# SAMD51_DevBoard.net
KiCad netlist of a schematic drawn in Altium Designer
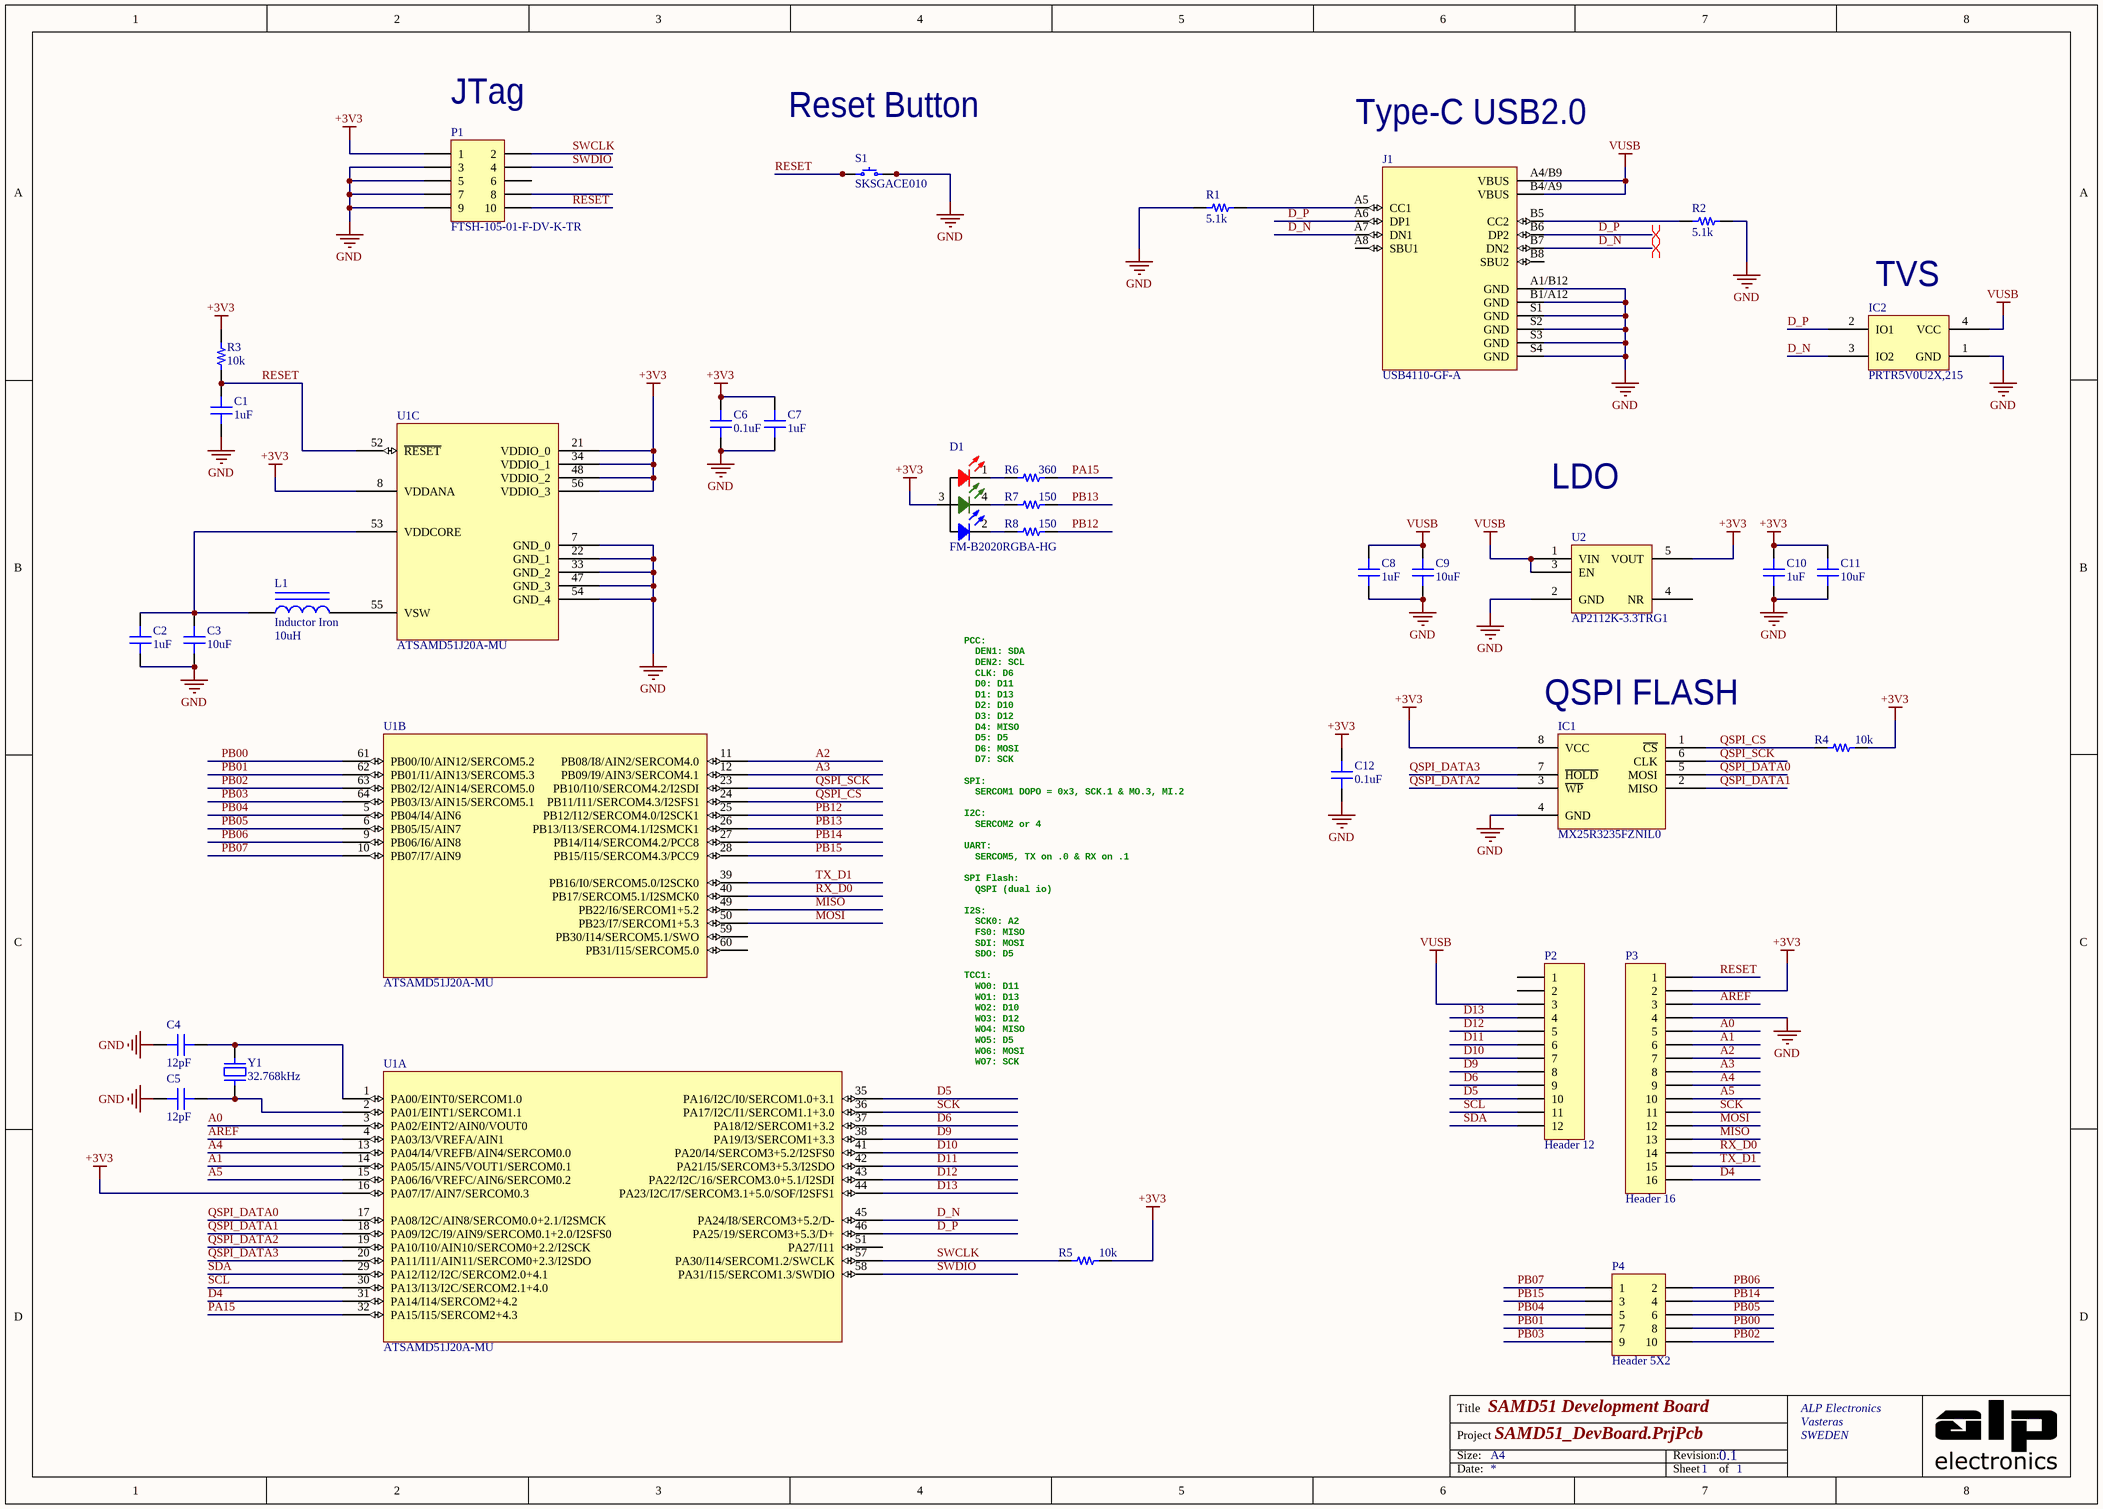
[diagram p0: SAMD51_DevBoard.SchDoc]

(export (version "E")
  (design (tool "Eeschema 10.0.6"))
  (components
    (comp (ref "C1")
      (value "1uF")
      (footprint "CAP 0603/1608")
      (description "CAP CER 1UF 16V X5R 0603")
      (fields (field (name "PART NUMBER") "C0603C105K4PACTU") (field (name "MANUFACTURER") "Kemet"))
      (libsource (lib "Celestial Library Database") (part "Capacitor"))
    )
    (comp (ref "C2")
      (value "1uF")
      (footprint "CAP 0603/1608")
      (description "CAP CER 1UF 16V X5R 0603")
      (fields (field (name "PART NUMBER") "C0603C105K4PACTU") (field (name "MANUFACTURER") "Kemet"))
      (libsource (lib "Celestial Library Database") (part "Capacitor"))
    )
    (comp (ref "C3")
      (value "10uF")
      (footprint "CAP 0603/1608")
      (description "CAP CER 10UF 6.3V X5R 0603")
      (fields
        (field (name "PART NUMBER") "GRM188R60J106ME47D")
        (field (name "MANUFACTURER") "Murata Electronics North America")
      )
      (libsource (lib "Celestial Library Database") (part "Capacitor"))
    )
    (comp (ref "C4")
      (value "12pF")
      (footprint "CAP 0603/1608")
      (description "CAP CER 12PF 50V C0G 0603")
      (fields
        (field (name "PART NUMBER") "C1608C0G1H120J080AA")
        (field (name "MANUFACTURER") "TDK Corporation")
      )
      (libsource (lib "Celestial Library Database") (part "Capacitor"))
    )
    (comp (ref "C5")
      (value "12pF")
      (footprint "CAP 0603/1608")
      (description "CAP CER 12PF 50V C0G 0603")
      (fields
        (field (name "PART NUMBER") "C1608C0G1H120J080AA")
        (field (name "MANUFACTURER") "TDK Corporation")
      )
      (libsource (lib "Celestial Library Database") (part "Capacitor"))
    )
    (comp (ref "C6")
      (value "0.1uF")
      (footprint "CAP 0603/1608")
      (description "CAP CER 0.1UF 16V X7R 0603")
      (fields
        (field (name "PART NUMBER") "CL10B104JO8NNNC")
        (field (name "MANUFACTURER") "Samsung Electro-Mechanics America, Inc.")
      )
      (libsource (lib "Celestial Library Database") (part "Capacitor"))
    )
    (comp (ref "C7")
      (value "1uF")
      (footprint "CAP 0603/1608")
      (description "CAP CER 1UF 16V X5R 0603")
      (fields (field (name "PART NUMBER") "C0603C105K4PACTU") (field (name "MANUFACTURER") "Kemet"))
      (libsource (lib "Celestial Library Database") (part "Capacitor"))
    )
    (comp (ref "C8")
      (value "1uF")
      (footprint "CAP 0603/1608")
      (description "CAP CER 1UF 16V X5R 0603")
      (fields (field (name "PART NUMBER") "C0603C105K4PACTU") (field (name "MANUFACTURER") "Kemet"))
      (libsource (lib "Celestial Library Database") (part "Capacitor"))
    )
    (comp (ref "C9")
      (value "10uF")
      (footprint "CAP 0603/1608")
      (description "CAP CER 10UF 6.3V X5R 0603")
      (fields
        (field (name "PART NUMBER") "GRM188R60J106ME47D")
        (field (name "MANUFACTURER") "Murata Electronics North America")
      )
      (libsource (lib "Celestial Library Database") (part "Capacitor"))
    )
    (comp (ref "C10")
      (value "1uF")
      (footprint "CAP 0603/1608")
      (description "CAP CER 1UF 16V X5R 0603")
      (fields (field (name "PART NUMBER") "C0603C105K4PACTU") (field (name "MANUFACTURER") "Kemet"))
      (libsource (lib "Celestial Library Database") (part "Capacitor"))
    )
    (comp (ref "C11")
      (value "10uF")
      (footprint "CAP 0603/1608")
      (description "CAP CER 10UF 6.3V X5R 0603")
      (fields
        (field (name "PART NUMBER") "GRM188R60J106ME47D")
        (field (name "MANUFACTURER") "Murata Electronics North America")
      )
      (libsource (lib "Celestial Library Database") (part "Capacitor"))
    )
    (comp (ref "C12")
      (value "0.1uF")
      (footprint "CAP 0603/1608")
      (description "CAP CER 0.1UF 16V X7R 0603")
      (fields
        (field (name "PART NUMBER") "CL10B104JO8NNNC")
        (field (name "MANUFACTURER") "Samsung Electro-Mechanics America, Inc.")
      )
      (libsource (lib "Celestial Library Database") (part "Capacitor"))
    )
    (comp (ref "D1")
      (value "FM-B2020RGBA-HG")
      (footprint "FM-B2020RGBA-HG")
      (description "RGB 615~630nmRed,515~535nmGreen,465~480nmBlue 2020")
      (fields (field (name "MANUFACTURER") "Foshan NationStar Optoelectronics"))
      (libsource (lib "Celestial Library Database") (part "RGB LED 4PIN"))
    )
    (comp (ref "IC1")
      (value "MX25R3235FZNIL0")
      (footprint "SPANSION WSON-8 6x5MM")
      (description "IC FLASH MEM 16MB SPI CMOS 8WSON")
      (fields (field (name "PART NUMBER") "S25FL116K0XNFI011") (field (name "MANUFACTURER") "Spansion"))
      (libsource (lib "Celestial Library Database") (part "SPANSION FLASH SPI 8PIN"))
    )
    (comp (ref "IC2")
      (value "PRTR5V0U2X,215")
      (footprint "SOT143B")
      (description "TVS DIODE 5.5VWM SOT143B")
      (fields (field (name "MANUFACTURER") "NXP Semiconductors"))
      (libsource (lib "Celestial Library Database") (part "NXP PRTR5V0U2X"))
    )
    (comp (ref "J1")
      (value "USB4110-GF-A")
      (footprint "USB4110-GF-A")
      (description "CONN USB 2.0 TYPE-C R/A SMT")
      (fields (field (name "MANUFACTURER") "GCT"))
      (libsource (lib "Celestial Library Database") (part "USB4110-GF-A"))
    )
    (comp (ref "L1")
      (value "Inductor Iron")
      (footprint "Component 3D Footprint:IND_Würth_74404020100")
      (description "Magnetic-Core Inductor")
      (fields (field (name "ALTIUM_VALUE") "10uH") (field (name "PUBLISHER") "Altium Limited"))
      (libsource (lib "Miscellaneous Devices") (part "Inductor Iron"))
    )
    (comp (ref "P1")
      (value "FTSH-105-01-F-DV-K-TR")
      (footprint "3D FootPrint_Backup:FTSH-105-01-F-DV-K-TR")
      (description "Header, 5-Pin, Dual row")
      (fields (field (name "PUBLISHER") "Altium Limited"))
      (libsource (lib "Miscellaneous Connectors") (part "Header 5X2"))
    )
    (comp (ref "P2")
      (value "Header 12")
      (footprint "HDR1X12")
      (description "Header, 12-Pin")
      (fields (field (name "PUBLISHER") "Altium Limited"))
      (libsource (lib "Miscellaneous Connectors") (part "Header 12"))
    )
    (comp (ref "P3")
      (value "Header 16")
      (footprint "HDR1X16")
      (description "Header, 16-Pin")
      (fields (field (name "PUBLISHER") "Altium Limited"))
      (libsource (lib "Miscellaneous Connectors") (part "Header 16"))
    )
    (comp (ref "P4")
      (value "Header 5X2")
      (footprint "HDR2X5")
      (description "Header, 5-Pin, Dual row")
      (fields (field (name "PUBLISHER") "Altium Limited"))
      (libsource (lib "Miscellaneous Connectors") (part "Header 5X2"))
    )
    (comp (ref "R1")
      (value "5.1k")
      (footprint "RES 0603/1608")
      (description "RES SMD 5.1K OHM 5% 1/10W 0603")
      (fields
        (field (name "PART NUMBER") "ERJ-3GEYJ512V")
        (field (name "MANUFACTURER") "Panasonic Electronic Components")
      )
      (libsource (lib "Celestial Library Database") (part "Resistor"))
    )
    (comp (ref "R2")
      (value "5.1k")
      (footprint "RES 0603/1608")
      (description "RES SMD 5.1K OHM 5% 1/10W 0603")
      (fields
        (field (name "PART NUMBER") "ERJ-3GEYJ512V")
        (field (name "MANUFACTURER") "Panasonic Electronic Components")
      )
      (libsource (lib "Celestial Library Database") (part "Resistor"))
    )
    (comp (ref "R3")
      (value "10k")
      (footprint "RES 0603/1608")
      (description "RES SMD 10K OHM 5% 1/10W 0603")
      (fields
        (field (name "PART NUMBER") "ERJ-3GEYJ103V")
        (field (name "MANUFACTURER") "Panasonic Electronic Components")
      )
      (libsource (lib "Celestial Library Database") (part "Resistor"))
    )
    (comp (ref "R4")
      (value "10k")
      (footprint "RES 0603/1608")
      (description "RES SMD 10K OHM 5% 1/10W 0603")
      (fields
        (field (name "PART NUMBER") "ERJ-3GEYJ103V")
        (field (name "MANUFACTURER") "Panasonic Electronic Components")
      )
      (libsource (lib "Celestial Library Database") (part "Resistor"))
    )
    (comp (ref "R5")
      (value "10k")
      (footprint "RES 0603/1608")
      (description "RES SMD 10K OHM 5% 1/10W 0603")
      (fields
        (field (name "PART NUMBER") "ERJ-3GEYJ103V")
        (field (name "MANUFACTURER") "Panasonic Electronic Components")
      )
      (libsource (lib "Celestial Library Database") (part "Resistor"))
    )
    (comp (ref "R6")
      (value "360")
      (footprint "RES 0603/1608")
      (description "RES SMD 360 OHM 5% 1/10W 0603")
      (fields
        (field (name "PART NUMBER") "ERJ-3GEYJ361V")
        (field (name "MANUFACTURER") "Panasonic Electronic Components")
      )
      (libsource (lib "Celestial Library Database") (part "Resistor"))
    )
    (comp (ref "R7")
      (value "150")
      (footprint "RES 0603/1608")
      (description "RES SMD 150 OHM 5% 1/10W 0603")
      (fields
        (field (name "PART NUMBER") "ERJ-3GEYJ151V")
        (field (name "MANUFACTURER") "Panasonic Electronic Components")
      )
      (libsource (lib "Celestial Library Database") (part "Resistor"))
    )
    (comp (ref "R8")
      (value "150")
      (footprint "RES 0603/1608")
      (description "RES SMD 150 OHM 5% 1/10W 0603")
      (fields
        (field (name "PART NUMBER") "ERJ-3GEYJ151V")
        (field (name "MANUFACTURER") "Panasonic Electronic Components")
      )
      (libsource (lib "Celestial Library Database") (part "Resistor"))
    )
    (comp (ref "S1")
      (value "SKSGACE010")
      (footprint "SKSGACE010")
      (description "SWITCH TACTILE SPST-NO 0.05A 16V")
      (fields (field (name "MANUFACTURER") "ALPS"))
      (libsource (lib "Celestial Library Database") (part "SPST-NO 4 PIN"))
    )
    (comp (ref "U1")
      (value "ATSAMD51J20A-MU")
      (footprint "SI LABS QFN-64_S")
      (description "IC MCU 32BIT 1MB FLASH 64VQFN")
      (fields (field (name "MANUFACTURER") "Microchip Technology"))
      (libsource (lib "Celestial Library Database") (part "MicroChip SAM D5x VQFN64"))
    )
    (comp (ref "U2")
      (value "AP2112K-3.3TRG1")
      (footprint "TI SOT-23-5 DBV")
      (description "IC REG LINEAR 3.3V 400MA SOT23-5")
      (fields (field (name "PART NUMBER") "TPS73633DBVT") (field (name "MANUFACTURER") "Texas Instruments"))
      (libsource (lib "Celestial Library Database") (part "TI TPS736xx"))
    )
    (comp (ref "Y1")
      (value "32.768kHz")
      (footprint "ABRACON ABS07")
      (description "CRYSTAL 32.7680KHZ 12.5PF SMD")
      (fields (field (name "PART NUMBER") "ABS07-32.768KHZ-T") (field (name "MANUFACTURER") "Abracon LLC"))
      (libsource (lib "Celestial Library Database") (part "Abracon Crystal ABS07"))
    )
  )
  (nets
    (net (code "1") (name "+3V3") (class "Default")
      (node (ref "C10") (pin "2") (pinfunction "2_2") (pintype "passive"))
      (node (ref "C11") (pin "2") (pinfunction "2_2") (pintype "passive"))
      (node (ref "C12") (pin "2") (pinfunction "2_2") (pintype "passive"))
      (node (ref "C6") (pin "2") (pinfunction "2_2") (pintype "passive"))
      (node (ref "C7") (pin "2") (pinfunction "2_2") (pintype "passive"))
      (node (ref "D1") (pin "3") (pinfunction "3_3") (pintype "passive"))
      (node (ref "IC1") (pin "8") (pinfunction "VCC_8") (pintype "passive"))
      (node (ref "P1") (pin "1") (pinfunction "1_1") (pintype "passive"))
      (node (ref "P3") (pin "2") (pinfunction "2_2") (pintype "passive"))
      (node (ref "R3") (pin "2") (pinfunction "2_2") (pintype "passive"))
      (node (ref "R4") (pin "2") (pinfunction "2_2") (pintype "passive"))
      (node (ref "R5") (pin "2") (pinfunction "2_2") (pintype "passive"))
      (node (ref "U1") (pin "16") (pinfunction "PA07/I7/AIN7/SERCOM0.3_16") (pintype "bidirectional"))
      (node (ref "U1") (pin "21") (pinfunction "VDDIO_0_21") (pintype "power_in"))
      (node (ref "U1") (pin "34") (pinfunction "VDDIO_1_34") (pintype "power_in"))
      (node (ref "U1") (pin "48") (pinfunction "VDDIO_2_48") (pintype "power_in"))
      (node (ref "U1") (pin "56") (pinfunction "VDDIO_3_56") (pintype "power_in"))
      (node (ref "U1") (pin "8") (pinfunction "VDDANA_8") (pintype "power_in"))
      (node (ref "U2") (pin "5") (pinfunction "VOUT_5") (pintype "passive"))
    )
    (net (code "2") (name "/A0") (class "Default")
      (node (ref "P3") (pin "5") (pinfunction "5_5") (pintype "passive"))
      (node (ref "U1") (pin "3") (pinfunction "PA02/EINT2/AIN0/VOUT0_3") (pintype "bidirectional"))
    )
    (net (code "3") (name "/A1") (class "Default")
      (node (ref "P3") (pin "6") (pinfunction "6_6") (pintype "passive"))
      (node (ref "U1") (pin "14") (pinfunction "PA05/I5/AIN5/VOUT1/SERCOM0.1_14") (pintype "bidirectional"))
    )
    (net (code "4") (name "/A2") (class "Default")
      (node (ref "P3") (pin "7") (pinfunction "7_7") (pintype "passive"))
      (node (ref "U1") (pin "11") (pinfunction "PB08/I8/AIN2/SERCOM4.0_11") (pintype "bidirectional"))
    )
    (net (code "5") (name "/A3") (class "Default")
      (node (ref "P3") (pin "8") (pinfunction "8_8") (pintype "passive"))
      (node (ref "U1") (pin "12") (pinfunction "PB09/I9/AIN3/SERCOM4.1_12") (pintype "bidirectional"))
    )
    (net (code "6") (name "/A4") (class "Default")
      (node (ref "P3") (pin "9") (pinfunction "9_9") (pintype "passive"))
      (node (ref "U1") (pin "13") (pinfunction "PA04/I4/VREFB/AIN4/SERCOM0.0_13") (pintype "bidirectional"))
    )
    (net (code "7") (name "/A5") (class "Default")
      (node (ref "P3") (pin "10") (pinfunction "10_10") (pintype "passive"))
      (node (ref "U1") (pin "15") (pinfunction "PA06/I6/VREFC/AIN6/SERCOM0.2_15") (pintype "bidirectional"))
    )
    (net (code "8") (name "/AREF") (class "Default")
      (node (ref "P3") (pin "3") (pinfunction "3_3") (pintype "passive"))
      (node (ref "U1") (pin "4") (pinfunction "PA03/I3/VREFA/AIN1_4") (pintype "bidirectional"))
    )
    (net (code "9") (name "/D4") (class "Default")
      (node (ref "P3") (pin "16") (pinfunction "16_16") (pintype "passive"))
      (node (ref "U1") (pin "31") (pinfunction "PA14/I14/SERCOM2+4.2_31") (pintype "bidirectional"))
    )
    (net (code "10") (name "/D5") (class "Default")
      (node (ref "P2") (pin "10") (pinfunction "10_10") (pintype "passive"))
      (node (ref "U1") (pin "35") (pinfunction "PA16/I2C/I0/SERCOM1.0+3.1_35") (pintype "bidirectional"))
    )
    (net (code "11") (name "/D6") (class "Default")
      (node (ref "P2") (pin "9") (pinfunction "9_9") (pintype "passive"))
      (node (ref "U1") (pin "37") (pinfunction "PA18/I2/SERCOM1+3.2_37") (pintype "bidirectional"))
    )
    (net (code "12") (name "/D9") (class "Default")
      (node (ref "P2") (pin "8") (pinfunction "8_8") (pintype "passive"))
      (node (ref "U1") (pin "38") (pinfunction "PA19/I3/SERCOM1+3.3_38") (pintype "bidirectional"))
    )
    (net (code "13") (name "/D10") (class "Default")
      (node (ref "P2") (pin "7") (pinfunction "7_7") (pintype "passive"))
      (node (ref "U1") (pin "41") (pinfunction "PA20/I4/SERCOM3+5.2/I2SFS0_41") (pintype "bidirectional"))
    )
    (net (code "14") (name "/D11") (class "Default")
      (node (ref "P2") (pin "6") (pinfunction "6_6") (pintype "passive"))
      (node (ref "U1") (pin "42") (pinfunction "PA21/I5/SERCOM3+5.3/I2SDO_42") (pintype "bidirectional"))
    )
    (net (code "15") (name "/D12") (class "Default")
      (node (ref "P2") (pin "5") (pinfunction "5_5") (pintype "passive"))
      (node (ref "U1") (pin "43") (pinfunction "PA22/I2C/16/SERCOM3.0+5.1/I2SDI_43") (pintype "bidirectional"))
    )
    (net (code "16") (name "/D13") (class "Default")
      (node (ref "P2") (pin "4") (pinfunction "4_4") (pintype "passive"))
      (node (ref "U1") (pin "44") (pinfunction "PA23/I2C/I7/SERCOM3.1+5.0/SOF/I2SFS1_44") (pintype "bidirectional"))
    )
    (net (code "17") (name "/D_N") (class "Default")
      (node (ref "IC2") (pin "3") (pinfunction "IO2_3") (pintype "passive"))
      (node (ref "J1") (pin "A7") (pinfunction "DN1_A7") (pintype "bidirectional"))
      (node (ref "J1") (pin "B7") (pinfunction "DN2_B7") (pintype "bidirectional"))
      (node (ref "U1") (pin "45") (pinfunction "PA24/I8/SERCOM3+5.2/D-_45") (pintype "bidirectional"))
    )
    (net (code "18") (name "/D_P") (class "Default")
      (node (ref "IC2") (pin "2") (pinfunction "IO1_2") (pintype "passive"))
      (node (ref "J1") (pin "A6") (pinfunction "DP1_A6") (pintype "bidirectional"))
      (node (ref "J1") (pin "B6") (pinfunction "DP2_B6") (pintype "bidirectional"))
      (node (ref "U1") (pin "46") (pinfunction "PA25/19/SERCOM3+5.3/D+_46") (pintype "bidirectional"))
    )
    (net (code "19") (name "/MISO") (class "Default")
      (node (ref "P3") (pin "13") (pinfunction "13_13") (pintype "passive"))
      (node (ref "U1") (pin "49") (pinfunction "PB22/I6/SERCOM1+5.2_49") (pintype "bidirectional"))
    )
    (net (code "20") (name "/MOSI") (class "Default")
      (node (ref "P3") (pin "12") (pinfunction "12_12") (pintype "passive"))
      (node (ref "U1") (pin "50") (pinfunction "PB23/I7/SERCOM1+5.3_50") (pintype "bidirectional"))
    )
    (net (code "21") (name "/PA15") (class "Default")
      (node (ref "R6") (pin "2") (pinfunction "2_2") (pintype "passive"))
      (node (ref "U1") (pin "32") (pinfunction "PA15/I15/SERCOM2+4.3_32") (pintype "bidirectional"))
    )
    (net (code "22") (name "/PB00") (class "Default")
      (node (ref "P4") (pin "8") (pinfunction "8_8") (pintype "passive"))
      (node (ref "U1") (pin "61") (pinfunction "PB00/I0/AIN12/SERCOM5.2_61") (pintype "bidirectional"))
    )
    (net (code "23") (name "/PB01") (class "Default")
      (node (ref "P4") (pin "7") (pinfunction "7_7") (pintype "passive"))
      (node (ref "U1") (pin "62") (pinfunction "PB01/I1/AIN13/SERCOM5.3_62") (pintype "bidirectional"))
    )
    (net (code "24") (name "/PB02") (class "Default")
      (node (ref "P4") (pin "10") (pinfunction "10_10") (pintype "passive"))
      (node (ref "U1") (pin "63") (pinfunction "PB02/I2/AIN14/SERCOM5.0_63") (pintype "bidirectional"))
    )
    (net (code "25") (name "/PB03") (class "Default")
      (node (ref "P4") (pin "9") (pinfunction "9_9") (pintype "passive"))
      (node (ref "U1") (pin "64") (pinfunction "PB03/I3/AIN15/SERCOM5.1_64") (pintype "bidirectional"))
    )
    (net (code "26") (name "/PB04") (class "Default")
      (node (ref "P4") (pin "5") (pinfunction "5_5") (pintype "passive"))
      (node (ref "U1") (pin "5") (pinfunction "PB04/I4/AIN6_5") (pintype "bidirectional"))
    )
    (net (code "27") (name "/PB05") (class "Default")
      (node (ref "P4") (pin "6") (pinfunction "6_6") (pintype "passive"))
      (node (ref "U1") (pin "6") (pinfunction "PB05/I5/AIN7_6") (pintype "bidirectional"))
    )
    (net (code "28") (name "/PB06") (class "Default")
      (node (ref "P4") (pin "2") (pinfunction "2_2") (pintype "passive"))
      (node (ref "U1") (pin "9") (pinfunction "PB06/I6/AIN8_9") (pintype "bidirectional"))
    )
    (net (code "29") (name "/PB07") (class "Default")
      (node (ref "P4") (pin "1") (pinfunction "1_1") (pintype "passive"))
      (node (ref "U1") (pin "10") (pinfunction "PB07/I7/AIN9_10") (pintype "bidirectional"))
    )
    (net (code "30") (name "/PB12") (class "Default")
      (node (ref "R8") (pin "2") (pinfunction "2_2") (pintype "passive"))
      (node (ref "U1") (pin "25") (pinfunction "PB12/I12/SERCOM4.0/I2SCK1_25") (pintype "bidirectional"))
    )
    (net (code "31") (name "/PB13") (class "Default")
      (node (ref "R7") (pin "2") (pinfunction "2_2") (pintype "passive"))
      (node (ref "U1") (pin "26") (pinfunction "PB13/I13/SERCOM4.1/I2SMCK1_26") (pintype "bidirectional"))
    )
    (net (code "32") (name "/PB14") (class "Default")
      (node (ref "P4") (pin "4") (pinfunction "4_4") (pintype "passive"))
      (node (ref "U1") (pin "27") (pinfunction "PB14/I14/SERCOM4.2/PCC8_27") (pintype "bidirectional"))
    )
    (net (code "33") (name "/PB15") (class "Default")
      (node (ref "P4") (pin "3") (pinfunction "3_3") (pintype "passive"))
      (node (ref "U1") (pin "28") (pinfunction "PB15/I15/SERCOM4.3/PCC9_28") (pintype "bidirectional"))
    )
    (net (code "34") (name "/QSPI_CS") (class "Default")
      (node (ref "IC1") (pin "1") (pinfunction "~{CS}_1") (pintype "passive"))
      (node (ref "R4") (pin "1") (pinfunction "1_1") (pintype "passive"))
      (node (ref "U1") (pin "24") (pinfunction "PB11/I11/SERCOM4.3/I2SFS1_24") (pintype "bidirectional"))
    )
    (net (code "35") (name "/QSPI_DATA0") (class "Default")
      (node (ref "IC1") (pin "5") (pinfunction "MOSI_5") (pintype "passive"))
      (node (ref "U1") (pin "17") (pinfunction "PA08/I2C/AIN8/SERCOM0.0+2.1/I2SMCK_17") (pintype "bidirectional"))
    )
    (net (code "36") (name "/QSPI_DATA1") (class "Default")
      (node (ref "IC1") (pin "2") (pinfunction "MISO_2") (pintype "passive"))
      (node (ref "U1") (pin "18") (pinfunction "PA09/I2C/I9/AIN9/SERCOM0.1+2.0/I2SFS0_18") (pintype "bidirectional"))
    )
    (net (code "37") (name "/QSPI_DATA2") (class "Default")
      (node (ref "IC1") (pin "3") (pinfunction "~{WP}_3") (pintype "passive"))
      (node (ref "U1") (pin "19") (pinfunction "PA10/I10/AIN10/SERCOM0+2.2/I2SCK_19") (pintype "bidirectional"))
    )
    (net (code "38") (name "/QSPI_DATA3") (class "Default")
      (node (ref "IC1") (pin "7") (pinfunction "~{HOLD}_7") (pintype "passive"))
      (node (ref "U1") (pin "20") (pinfunction "PA11/I11/AIN11/SERCOM0+2.3/I2SDO_20") (pintype "bidirectional"))
    )
    (net (code "39") (name "/QSPI_SCK") (class "Default")
      (node (ref "IC1") (pin "6") (pinfunction "CLK_6") (pintype "passive"))
      (node (ref "U1") (pin "23") (pinfunction "PB10/I10/SERCOM4.2/I2SDI_23") (pintype "bidirectional"))
    )
    (net (code "40") (name "/RESET") (class "Default")
      (node (ref "C1") (pin "2") (pinfunction "2_2") (pintype "passive"))
      (node (ref "P1") (pin "10") (pinfunction "10_10") (pintype "passive"))
      (node (ref "P3") (pin "1") (pinfunction "1_1") (pintype "passive"))
      (node (ref "R3") (pin "1") (pinfunction "1_1") (pintype "passive"))
      (node (ref "S1") (pin "1") (pinfunction "1_1") (pintype "passive"))
      (node (ref "S1") (pin "2") (pinfunction "2_2") (pintype "passive"))
      (node (ref "U1") (pin "52") (pinfunction "~{RESET}_52") (pintype "bidirectional"))
    )
    (net (code "41") (name "/RX_D0") (class "Default")
      (node (ref "P3") (pin "14") (pinfunction "14_14") (pintype "passive"))
      (node (ref "U1") (pin "40") (pinfunction "PB17/SERCOM5.1/I2SMCK0_40") (pintype "bidirectional"))
    )
    (net (code "42") (name "/SCK") (class "Default")
      (node (ref "P3") (pin "11") (pinfunction "11_11") (pintype "passive"))
      (node (ref "U1") (pin "36") (pinfunction "PA17/I2C/I1/SERCOM1.1+3.0_36") (pintype "bidirectional"))
    )
    (net (code "43") (name "/SCL") (class "Default")
      (node (ref "P2") (pin "11") (pinfunction "11_11") (pintype "passive"))
      (node (ref "U1") (pin "30") (pinfunction "PA13/I13/I2C/SERCOM2.1+4.0_30") (pintype "bidirectional"))
    )
    (net (code "44") (name "/SDA") (class "Default")
      (node (ref "P2") (pin "12") (pinfunction "12_12") (pintype "passive"))
      (node (ref "U1") (pin "29") (pinfunction "PA12/I12/I2C/SERCOM2.0+4.1_29") (pintype "bidirectional"))
    )
    (net (code "45") (name "/SWCLK") (class "Default")
      (node (ref "P1") (pin "2") (pinfunction "2_2") (pintype "passive"))
      (node (ref "R5") (pin "1") (pinfunction "1_1") (pintype "passive"))
      (node (ref "U1") (pin "57") (pinfunction "PA30/I14/SERCOM1.2/SWCLK_57") (pintype "bidirectional"))
    )
    (net (code "46") (name "/SWDIO") (class "Default")
      (node (ref "P1") (pin "4") (pinfunction "4_4") (pintype "passive"))
      (node (ref "U1") (pin "58") (pinfunction "PA31/I15/SERCOM1.3/SWDIO_58") (pintype "bidirectional"))
    )
    (net (code "47") (name "/TX_D1") (class "Default")
      (node (ref "P3") (pin "15") (pinfunction "15_15") (pintype "passive"))
      (node (ref "U1") (pin "39") (pinfunction "PB16/I0/SERCOM5.0/I2SCK0_39") (pintype "bidirectional"))
    )
    (net (code "48") (name "GND") (class "Default")
      (node (ref "C1") (pin "1") (pinfunction "1_1") (pintype "passive"))
      (node (ref "C10") (pin "1") (pinfunction "1_1") (pintype "passive"))
      (node (ref "C11") (pin "1") (pinfunction "1_1") (pintype "passive"))
      (node (ref "C12") (pin "1") (pinfunction "1_1") (pintype "passive"))
      (node (ref "C2") (pin "1") (pinfunction "1_1") (pintype "passive"))
      (node (ref "C3") (pin "1") (pinfunction "1_1") (pintype "passive"))
      (node (ref "C4") (pin "1") (pinfunction "1_1") (pintype "passive"))
      (node (ref "C5") (pin "1") (pinfunction "1_1") (pintype "passive"))
      (node (ref "C6") (pin "1") (pinfunction "1_1") (pintype "passive"))
      (node (ref "C7") (pin "1") (pinfunction "1_1") (pintype "passive"))
      (node (ref "C8") (pin "1") (pinfunction "1_1") (pintype "passive"))
      (node (ref "C9") (pin "1") (pinfunction "1_1") (pintype "passive"))
      (node (ref "IC1") (pin "4") (pinfunction "GND_4") (pintype "passive"))
      (node (ref "IC2") (pin "1") (pinfunction "GND_1") (pintype "passive"))
      (node (ref "J1") (pin "A1/B12") (pinfunction "GND_A1/B12") (pintype "power_in"))
      (node (ref "J1") (pin "B1/A12") (pinfunction "GND_B1/A12") (pintype "power_in"))
      (node (ref "J1") (pin "S1") (pinfunction "GND_S1") (pintype "power_in"))
      (node (ref "J1") (pin "S2") (pinfunction "GND_S2") (pintype "power_in"))
      (node (ref "J1") (pin "S3") (pinfunction "GND_S3") (pintype "power_in"))
      (node (ref "J1") (pin "S4") (pinfunction "GND_S4") (pintype "power_in"))
      (node (ref "P1") (pin "3") (pinfunction "3_3") (pintype "passive"))
      (node (ref "P1") (pin "5") (pinfunction "5_5") (pintype "passive"))
      (node (ref "P1") (pin "7") (pinfunction "7_7") (pintype "passive"))
      (node (ref "P1") (pin "9") (pinfunction "9_9") (pintype "passive"))
      (node (ref "P3") (pin "4") (pinfunction "4_4") (pintype "passive"))
      (node (ref "R1") (pin "1") (pinfunction "1_1") (pintype "passive"))
      (node (ref "R2") (pin "2") (pinfunction "2_2") (pintype "passive"))
      (node (ref "S1") (pin "3") (pinfunction "3_3") (pintype "passive"))
      (node (ref "S1") (pin "4") (pinfunction "4_4") (pintype "passive"))
      (node (ref "U1") (pin "22") (pinfunction "GND_1_22") (pintype "power_in"))
      (node (ref "U1") (pin "33") (pinfunction "GND_2_33") (pintype "power_in"))
      (node (ref "U1") (pin "47") (pinfunction "GND_3_47") (pintype "power_in"))
      (node (ref "U1") (pin "54") (pinfunction "GND_4_54") (pintype "power_in"))
      (node (ref "U1") (pin "7") (pinfunction "GND_0_7") (pintype "power_in"))
      (node (ref "U2") (pin "2") (pinfunction "GND_2") (pintype "passive"))
    )
    (net (code "49") (name "Net-(D1-Pad1)") (class "Default")
      (node (ref "D1") (pin "1") (pinfunction "1_1") (pintype "passive"))
      (node (ref "R6") (pin "1") (pinfunction "1_1") (pintype "passive"))
    )
    (net (code "50") (name "Net-(D1-Pad2)") (class "Default")
      (node (ref "D1") (pin "2") (pinfunction "2_2") (pintype "passive"))
      (node (ref "R8") (pin "1") (pinfunction "1_1") (pintype "passive"))
    )
    (net (code "51") (name "Net-(D1-Pad4)") (class "Default")
      (node (ref "D1") (pin "4") (pinfunction "4_4") (pintype "passive"))
      (node (ref "R7") (pin "1") (pinfunction "1_1") (pintype "passive"))
    )
    (net (code "52") (name "Net-(J1-CC1)") (class "Default")
      (node (ref "J1") (pin "A5") (pinfunction "CC1_A5") (pintype "bidirectional"))
      (node (ref "R1") (pin "2") (pinfunction "2_2") (pintype "passive"))
    )
    (net (code "53") (name "Net-(J1-CC2)") (class "Default")
      (node (ref "J1") (pin "B5") (pinfunction "CC2_B5") (pintype "bidirectional"))
      (node (ref "R2") (pin "1") (pinfunction "1_1") (pintype "passive"))
    )
    (net (code "54") (name "Net-(U1A-PA00{slash}EINT0{slash}SERCOM1.0)") (class "Default")
      (node (ref "C4") (pin "2") (pinfunction "2_2") (pintype "passive"))
      (node (ref "U1") (pin "1") (pinfunction "PA00/EINT0/SERCOM1.0_1") (pintype "bidirectional"))
      (node (ref "Y1") (pin "2") (pinfunction "2_2") (pintype "passive"))
    )
    (net (code "55") (name "Net-(U1A-PA01{slash}EINT1{slash}SERCOM1.1)") (class "Default")
      (node (ref "C5") (pin "2") (pinfunction "2_2") (pintype "passive"))
      (node (ref "U1") (pin "2") (pinfunction "PA01/EINT1/SERCOM1.1_2") (pintype "bidirectional"))
      (node (ref "Y1") (pin "1") (pinfunction "1_1") (pintype "passive"))
    )
    (net (code "56") (name "Net-(U1C-VDDCORE)") (class "Default")
      (node (ref "C2") (pin "2") (pinfunction "2_2") (pintype "passive"))
      (node (ref "C3") (pin "2") (pinfunction "2_2") (pintype "passive"))
      (node (ref "L1") (pin "1") (pinfunction "1_1") (pintype "passive"))
      (node (ref "U1") (pin "53") (pinfunction "VDDCORE_53") (pintype "power_in"))
    )
    (net (code "57") (name "Net-(U1C-VSW)") (class "Default")
      (node (ref "L1") (pin "2") (pinfunction "2_2") (pintype "passive"))
      (node (ref "U1") (pin "55") (pinfunction "VSW_55") (pintype "power_in"))
    )
    (net (code "58") (name "VUSB") (class "Default")
      (node (ref "C8") (pin "2") (pinfunction "2_2") (pintype "passive"))
      (node (ref "C9") (pin "2") (pinfunction "2_2") (pintype "passive"))
      (node (ref "IC2") (pin "4") (pinfunction "VCC_4") (pintype "passive"))
      (node (ref "J1") (pin "A4/B9") (pinfunction "VBUS_A4/B9") (pintype "power_in"))
      (node (ref "J1") (pin "B4/A9") (pinfunction "VBUS_B4/A9") (pintype "power_in"))
      (node (ref "P2") (pin "3") (pinfunction "3_3") (pintype "passive"))
      (node (ref "U2") (pin "1") (pinfunction "VIN_1") (pintype "passive"))
      (node (ref "U2") (pin "3") (pinfunction "EN_3") (pintype "passive"))
    )
    (net (code "59") (name "unconnected-(J1-SBU1-PadA8)") (class "Default")
      (node (ref "J1") (pin "A8") (pinfunction "SBU1_A8") (pintype "bidirectional"))
    )
    (net (code "60") (name "unconnected-(J1-SBU2-PadB8)") (class "Default")
      (node (ref "J1") (pin "B8") (pinfunction "SBU2_B8") (pintype "bidirectional"))
    )
    (net (code "61") (name "unconnected-(P1-Pad6)") (class "Default")
      (node (ref "P1") (pin "6") (pinfunction "6_6") (pintype "passive"))
    )
    (net (code "62") (name "unconnected-(P1-Pad8)") (class "Default")
      (node (ref "P1") (pin "8") (pinfunction "8_8") (pintype "passive"))
    )
    (net (code "63") (name "unconnected-(P2-Pad1)") (class "Default")
      (node (ref "P2") (pin "1") (pinfunction "1_1") (pintype "passive"))
    )
    (net (code "64") (name "unconnected-(P2-Pad2)") (class "Default")
      (node (ref "P2") (pin "2") (pinfunction "2_2") (pintype "passive"))
    )
    (net (code "65") (name "unconnected-(U1A-PA27{slash}I11-Pad51)") (class "Default")
      (node (ref "U1") (pin "51") (pinfunction "PA27/I11_51") (pintype "bidirectional"))
    )
    (net (code "66") (name "unconnected-(U1B-PB30{slash}I14{slash}SERCOM5.1{slash}SWO-Pad59)") (class "Default")
      (node (ref "U1") (pin "59") (pinfunction "PB30/I14/SERCOM5.1/SWO_59") (pintype "bidirectional"))
    )
    (net (code "67") (name "unconnected-(U1B-PB31{slash}I15{slash}SERCOM5.0-Pad60)") (class "Default")
      (node (ref "U1") (pin "60") (pinfunction "PB31/I15/SERCOM5.0_60") (pintype "bidirectional"))
    )
    (net (code "68") (name "unconnected-(U2-NR-Pad4)") (class "Default")
      (node (ref "U2") (pin "4") (pinfunction "NR_4") (pintype "passive"))
    )
  )
)
